# Jacdac_3D_Magnetometer.net
KiCad netlist of a schematic drawn in EAGLE
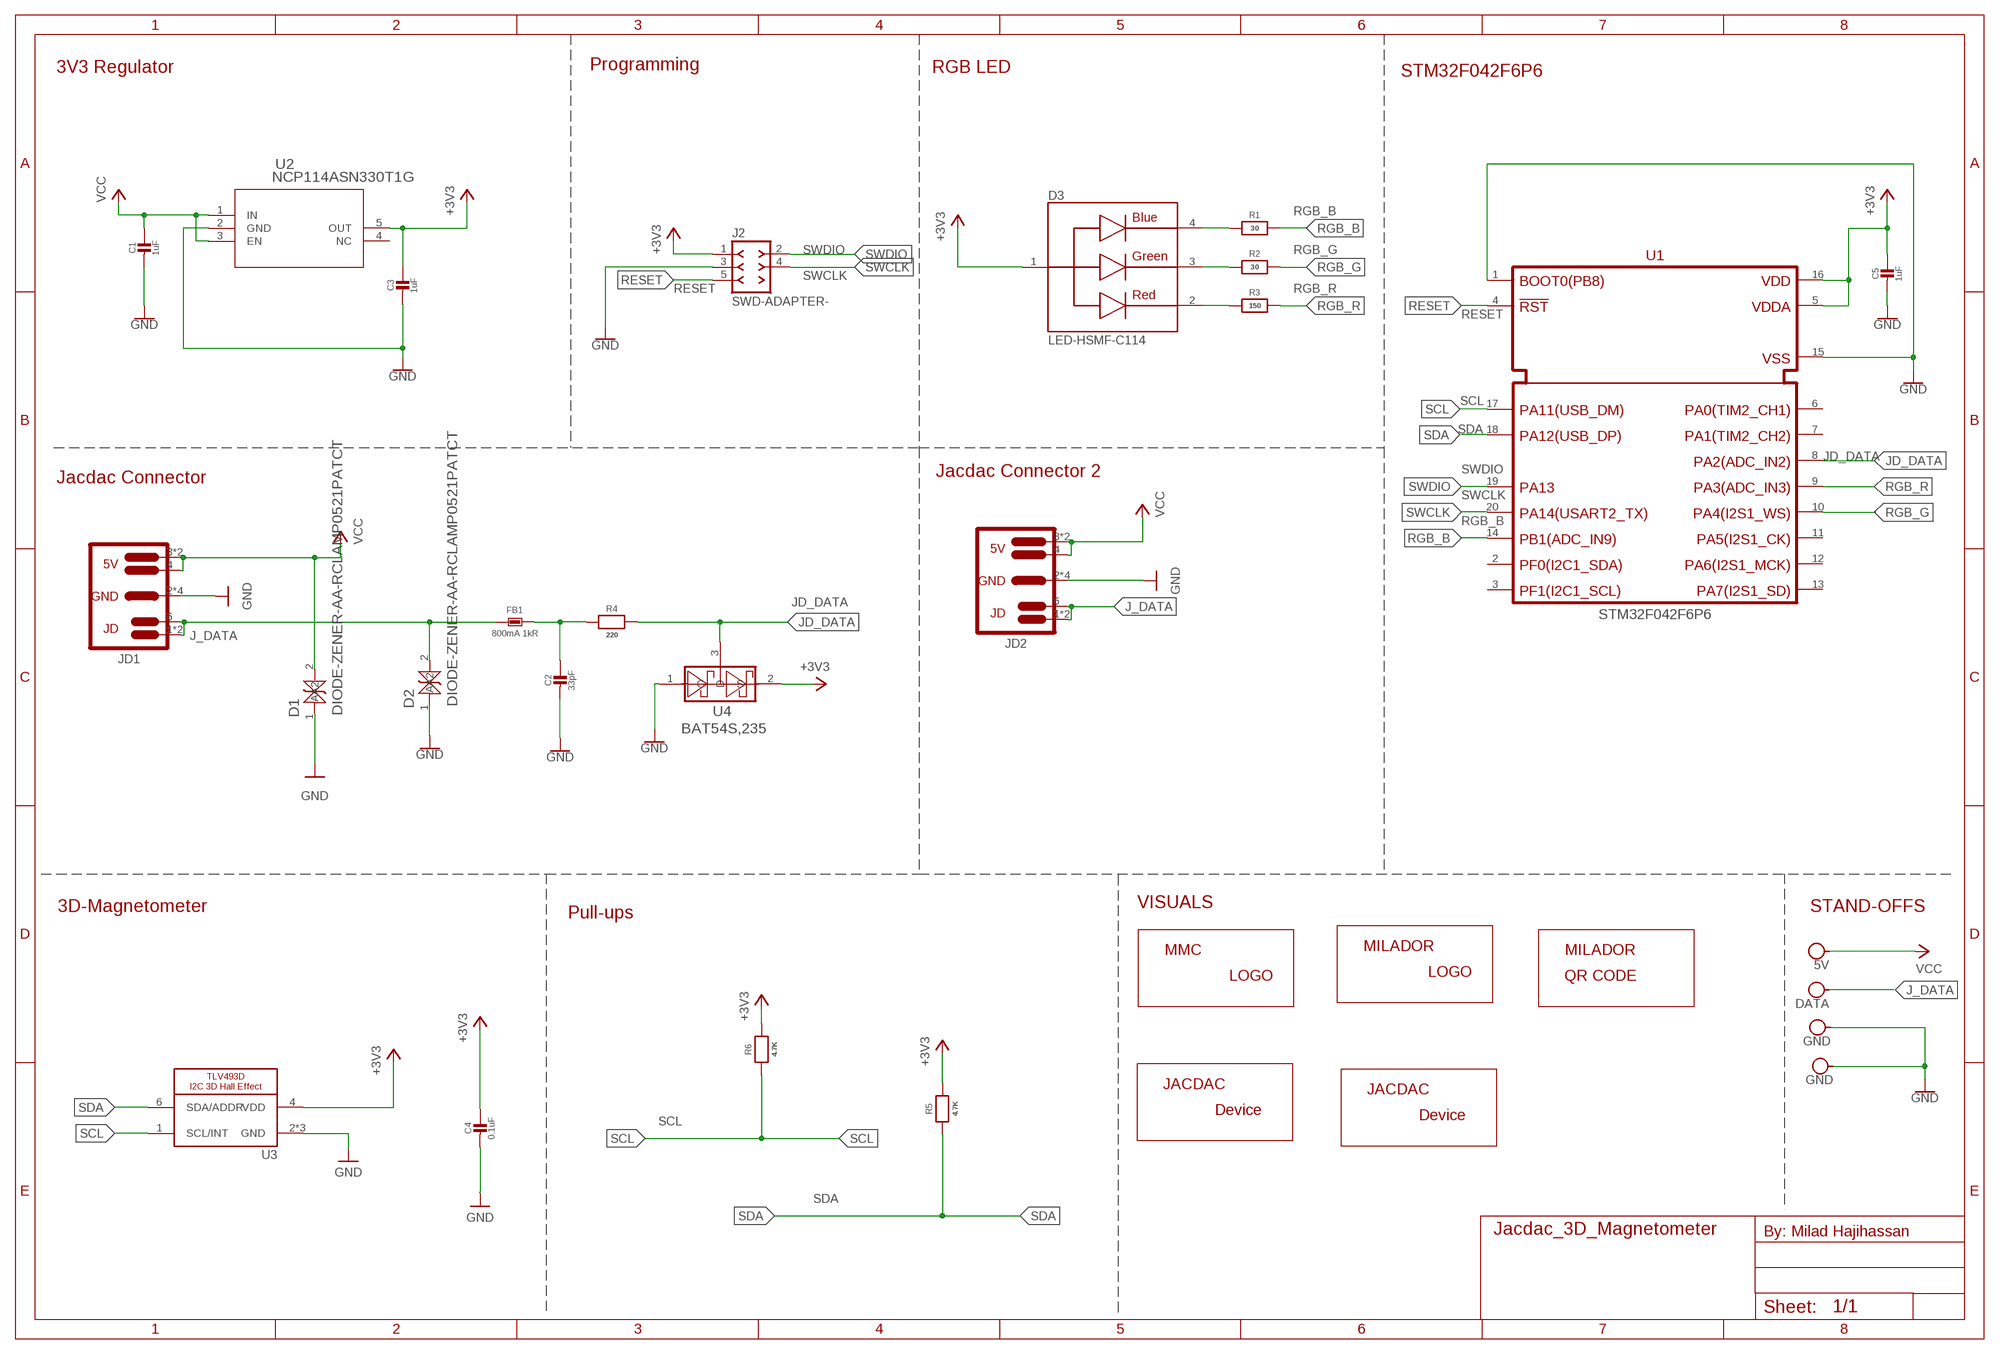
[diagram p0: schematic, sheet 1]

(export (version "E")
  (design (tool "Eeschema 10.0.6"))
  (components
    (comp (ref "C1")
      (value "1uF")
      (footprint "eagle-import:0603-NO")
      (libsource (lib "eagle-import") (part "CAP_CERAMIC-0603-NO"))
    )
    (comp (ref "C2")
      (value "33pF")
      (footprint "eagle-import:0603")
      (libsource (lib "eagle-import") (part "CAP_CERAMIC-0603"))
    )
    (comp (ref "C3")
      (value "1uF")
      (footprint "eagle-import:0603-NO")
      (libsource (lib "eagle-import") (part "CAP_CERAMIC-0603-NO"))
    )
    (comp (ref "C4")
      (value "0.1uF")
      (footprint "eagle-import:0603-NO")
      (libsource (lib "eagle-import") (part "CAP_CERAMIC-0603-NO"))
    )
    (comp (ref "C5")
      (value "1uF")
      (footprint "eagle-import:0603")
      (libsource (lib "eagle-import") (part "CAP_CERAMIC-0603"))
    )
    (comp (ref "D1")
      (value "DIODE-ZENER-AA-RCLAMP0521PATCT")
      (footprint "eagle-import:DIODE-ZENER-0402")
      (fields
        (field (name "MANUFACTURER_PART_NUMBER") "RCLAMP0521PATCT")
        (field (name "COPYRIGHT") "Copyright (C) 2021 Ultra Librarian. All rights reserved.")
      )
      (libsource (lib "eagle-import") (part "DIODE-ZENER-AA-RCLAMP0521PATCT"))
    )
    (comp (ref "D2")
      (value "DIODE-ZENER-AA-RCLAMP0521PATCT")
      (footprint "eagle-import:DIODE-ZENER-0402")
      (fields
        (field (name "MANUFACTURER_PART_NUMBER") "RCLAMP0521PATCT")
        (field (name "COPYRIGHT") "Copyright (C) 2021 Ultra Librarian. All rights reserved.")
      )
      (libsource (lib "eagle-import") (part "DIODE-ZENER-AA-RCLAMP0521PATCT"))
    )
    (comp (ref "D3")
      (value "LED-HSMF-C114")
      (footprint "eagle-import:DIOSC160X150X35-4N")
      (fields (field (name "MF") "Broadcom Limited") (field (name "MP") "HSMF-C114"))
      (libsource (lib "eagle-import") (part "LED-HSMF-C114"))
    )
    (comp (ref "FB1")
      (value "800mA 1kR")
      (footprint "eagle-import:0603-NO")
      (libsource (lib "eagle-import") (part "FERRITE-BEAD-0603-NO"))
    )
    (comp (ref "J2")
      (value "SWD-ADAPTER-")
      (footprint "eagle-import:SWD-ADAPTER")
      (libsource (lib "eagle-import") (part "SWD-ADAPTER-"))
    )
    (comp (ref "J3")
      (value "5V")
      (footprint "eagle-import:M3-HOLE-PWR-OUTL")
      (libsource (lib "eagle-import") (part "JACDAC-M3-PWR-OUTL"))
    )
    (comp (ref "J4")
      (value "DATA")
      (footprint "eagle-import:M3-HOLE-DATA-NOTCH")
      (libsource (lib "eagle-import") (part "JACDAC-M3-DATA-NOTCH"))
    )
    (comp (ref "J5")
      (value "GND")
      (footprint "eagle-import:M3-HOLE-GND")
      (libsource (lib "eagle-import") (part "JACDAC-M3-GND"))
    )
    (comp (ref "J6")
      (value "GND")
      (footprint "eagle-import:M3-HOLE-GND")
      (libsource (lib "eagle-import") (part "JACDAC-M3-GND"))
    )
    (comp (ref "JD1")
      (value "JACDAC-EDGE-OUTIE")
      (footprint "eagle-import:JD-EDGE-OUTIE")
      (libsource (lib "eagle-import") (part "JACDAC-EDGE-OUTIE"))
    )
    (comp (ref "JD2")
      (value "JACDAC-EDGE-OUTIE")
      (footprint "eagle-import:JD-EDGE-OUTIE")
      (libsource (lib "eagle-import") (part "JACDAC-EDGE-OUTIE"))
    )
    (comp (ref "LABEL_JACDAC_PS")
      (value "MILADOR-JACDAC-DEVICE-MAGNETOMETER")
      (footprint "eagle-import:JACDAC-3D-MAGNETOMETER")
      (libsource (lib "eagle-import") (part "MILADOR-JACDAC-DEVICE-MAGNETOMETER"))
    )
    (comp (ref "LABEL_MILADOR")
      (value "MILADOR-LOGO-")
      (footprint "eagle-import:MILADOR_LOGO1")
      (libsource (lib "eagle-import") (part "MILADOR-LOGO-"))
    )
    (comp (ref "LABEL_QR_CODE")
      (value "MILADOR-QR-CODE-JACDAC-MAGNETOMETER")
      (footprint "eagle-import:MILADOR_QR_JACDAC_MAGNETOMETER")
      (libsource (lib "eagle-import") (part "MILADOR-QR-CODE-JACDAC-MAGNETOMETER"))
    )
    (comp (ref "LABEL_TLV493D")
      (value "MILADOR-JACDAC-DEVICE-TLV493D")
      (footprint "eagle-import:JACDAC-TLV493D")
      (libsource (lib "eagle-import") (part "MILADOR-JACDAC-DEVICE-TLV493D"))
    )
    (comp (ref "MMC_LOGO")
      (value "MMC_LOGO-XSM")
      (footprint "eagle-import:MMC_X-SMALL_LOGO")
      (libsource (lib "eagle-import") (part "MMC_LOGO-XSM"))
    )
    (comp (ref "R1")
      (value "30")
      (footprint "eagle-import:0603")
      (libsource (lib "eagle-import") (part "RESISTOR-0603"))
    )
    (comp (ref "R2")
      (value "30")
      (footprint "eagle-import:0603")
      (libsource (lib "eagle-import") (part "RESISTOR-0603"))
    )
    (comp (ref "R3")
      (value "150")
      (footprint "eagle-import:0603")
      (libsource (lib "eagle-import") (part "RESISTOR-0603"))
    )
    (comp (ref "R4")
      (value "220")
      (footprint "eagle-import:0603")
      (libsource (lib "eagle-import") (part "RESISTOR-0603"))
    )
    (comp (ref "R5")
      (value "4.7K")
      (footprint "eagle-import:0603")
      (libsource (lib "eagle-import") (part "RESISTOR-0603"))
    )
    (comp (ref "R6")
      (value "4.7K")
      (footprint "eagle-import:0603")
      (libsource (lib "eagle-import") (part "RESISTOR-0603"))
    )
    (comp (ref "U1")
      (value "STM32F042F6P6")
      (footprint "eagle-import:TSSOP20")
      (libsource (lib "eagle-import") (part "STM32F042F6P6"))
    )
    (comp (ref "U2")
      (value "NCP114ASN330T1G")
      (footprint "eagle-import:TSOP-5_ONS")
      (fields (field (name "COPYRIGHT") "Copyright (C) 2021 Ultra Librarian. All rights reserved."))
      (libsource (lib "eagle-import") (part "NCP114ASN330T1G"))
    )
    (comp (ref "U3")
      (value "TLV493D")
      (footprint "eagle-import:SOT23-6")
      (libsource (lib "eagle-import") (part "TLV493D"))
    )
    (comp (ref "U4")
      (value "BAT54S,235")
      (footprint "eagle-import:SOT23-3")
      (fields (field (name "MF") "Diodes") (field (name "MP") "BSS138-7-F"))
      (libsource (lib "eagle-import") (part "BAT54S,235"))
    )
  )
  (nets
    (net (code "1") (name "+3V3") (class "Default")
      (node (ref "C3") (pin "1") (pinfunction "1_1") (pintype "passive"))
      (node (ref "C4") (pin "1") (pinfunction "1_1") (pintype "passive"))
      (node (ref "C5") (pin "1") (pinfunction "1_1") (pintype "passive"))
      (node (ref "D3") (pin "1") (pinfunction "1_1") (pintype "passive"))
      (node (ref "J2") (pin "1") (pinfunction "VCC_1_1") (pintype "passive"))
      (node (ref "R5") (pin "2") (pinfunction "2_2") (pintype "passive"))
      (node (ref "R6") (pin "2") (pinfunction "2_2") (pintype "passive"))
      (node (ref "U1") (pin "16") (pinfunction "VDD_16") (pintype "input"))
      (node (ref "U1") (pin "5") (pinfunction "VDDA_5") (pintype "input"))
      (node (ref "U2") (pin "5") (pinfunction "OUT_5") (pintype "power_in"))
      (node (ref "U3") (pin "4") (pinfunction "VDD_4") (pintype "power_in"))
      (node (ref "U4") (pin "2") (pinfunction "S_2") (pintype "passive"))
    )
    (net (code "2") (name "GND") (class "Default")
      (node (ref "C1") (pin "2") (pinfunction "2_2") (pintype "passive"))
      (node (ref "C2") (pin "2") (pinfunction "2_2") (pintype "passive"))
      (node (ref "C3") (pin "2") (pinfunction "2_2") (pintype "passive"))
      (node (ref "C4") (pin "2") (pinfunction "2_2") (pintype "passive"))
      (node (ref "C5") (pin "2") (pinfunction "2_2") (pintype "passive"))
      (node (ref "D1") (pin "1") (pinfunction "A_1") (pintype "passive"))
      (node (ref "D2") (pin "1") (pinfunction "A_1") (pintype "passive"))
      (node (ref "J2") (pin "3") (pinfunction "GND_3_3") (pintype "passive"))
      (node (ref "J5") (pin "H") (pinfunction "P$1_H") (pintype "bidirectional"))
      (node (ref "J6") (pin "H") (pinfunction "P$1_H") (pintype "bidirectional"))
      (node (ref "JD1") (pin "2") (pinfunction "1_2") (pintype "power_in"))
      (node (ref "JD1") (pin "5") (pinfunction "1_5") (pintype "power_in"))
      (node (ref "JD1") (pin "P$2") (pinfunction "1_P$2") (pintype "power_in"))
      (node (ref "JD1") (pin "P$4") (pinfunction "1_P$4") (pintype "power_in"))
      (node (ref "JD2") (pin "2") (pinfunction "1_2") (pintype "power_in"))
      (node (ref "JD2") (pin "5") (pinfunction "1_5") (pintype "power_in"))
      (node (ref "JD2") (pin "P$2") (pinfunction "1_P$2") (pintype "power_in"))
      (node (ref "JD2") (pin "P$4") (pinfunction "1_P$4") (pintype "power_in"))
      (node (ref "U1") (pin "1") (pinfunction "BOOT0_1") (pintype "input"))
      (node (ref "U1") (pin "15") (pinfunction "VSS_15") (pintype "input"))
      (node (ref "U2") (pin "2") (pinfunction "GND_2") (pintype "passive"))
      (node (ref "U3") (pin "2") (pinfunction "GND_2") (pintype "power_in"))
      (node (ref "U3") (pin "3") (pinfunction "GND_3") (pintype "power_in"))
      (node (ref "U3") (pin "5") (pinfunction "GND_5") (pintype "power_in"))
      (node (ref "U4") (pin "1") (pinfunction "G_1") (pintype "passive"))
    )
    (net (code "3") (name "JD_DATA") (class "Default")
      (node (ref "R4") (pin "2") (pinfunction "2_2") (pintype "passive"))
      (node (ref "U1") (pin "8") (pinfunction "PA2_8") (pintype "bidirectional"))
      (node (ref "U4") (pin "3") (pinfunction "D_3") (pintype "passive"))
    )
    (net (code "4") (name "J_DATA") (class "Default")
      (node (ref "D2") (pin "2") (pinfunction "A2_2") (pintype "passive"))
      (node (ref "FB1") (pin "2") (pinfunction "2_2") (pintype "passive"))
      (node (ref "J4") (pin "H") (pinfunction "P$1_H") (pintype "bidirectional"))
      (node (ref "JD1") (pin "1") (pinfunction "2_1") (pintype "bidirectional"))
      (node (ref "JD1") (pin "6") (pinfunction "6_6") (pintype "bidirectional"))
      (node (ref "JD1") (pin "P$3") (pinfunction "2_P$3") (pintype "bidirectional"))
      (node (ref "JD2") (pin "1") (pinfunction "2_1") (pintype "bidirectional"))
      (node (ref "JD2") (pin "6") (pinfunction "6_6") (pintype "bidirectional"))
      (node (ref "JD2") (pin "P$3") (pinfunction "2_P$3") (pintype "bidirectional"))
    )
    (net (code "5") (name "Net-(C2-Pad1)") (class "Default")
      (node (ref "C2") (pin "1") (pinfunction "1_1") (pintype "passive"))
      (node (ref "FB1") (pin "1") (pinfunction "1_1") (pintype "passive"))
      (node (ref "R4") (pin "1") (pinfunction "1_1") (pintype "passive"))
    )
    (net (code "6") (name "Net-(D3-Pad2)") (class "Default")
      (node (ref "D3") (pin "2") (pinfunction "2_2") (pintype "passive"))
      (node (ref "R3") (pin "1") (pinfunction "1_1") (pintype "passive"))
    )
    (net (code "7") (name "Net-(D3-Pad3)") (class "Default")
      (node (ref "D3") (pin "3") (pinfunction "3_3") (pintype "passive"))
      (node (ref "R2") (pin "1") (pinfunction "1_1") (pintype "passive"))
    )
    (net (code "8") (name "Net-(D3-Pad4)") (class "Default")
      (node (ref "D3") (pin "4") (pinfunction "4_4") (pintype "passive"))
      (node (ref "R1") (pin "1") (pinfunction "1_1") (pintype "passive"))
    )
    (net (code "9") (name "RESET") (class "Default")
      (node (ref "J2") (pin "5") (pinfunction "RESET_5_5") (pintype "passive"))
      (node (ref "U1") (pin "4") (pinfunction "~{RST}_4") (pintype "input"))
    )
    (net (code "10") (name "RGB_B") (class "Default")
      (node (ref "R1") (pin "2") (pinfunction "2_2") (pintype "passive"))
      (node (ref "U1") (pin "14") (pinfunction "PB1_14") (pintype "bidirectional"))
    )
    (net (code "11") (name "RGB_G") (class "Default")
      (node (ref "R2") (pin "2") (pinfunction "2_2") (pintype "passive"))
      (node (ref "U1") (pin "10") (pinfunction "PA4_10") (pintype "bidirectional"))
    )
    (net (code "12") (name "RGB_R") (class "Default")
      (node (ref "R3") (pin "2") (pinfunction "2_2") (pintype "passive"))
      (node (ref "U1") (pin "9") (pinfunction "PA3_9") (pintype "bidirectional"))
    )
    (net (code "13") (name "SCL") (class "Default")
      (node (ref "R6") (pin "1") (pinfunction "1_1") (pintype "passive"))
      (node (ref "U1") (pin "17") (pinfunction "PA11_17") (pintype "bidirectional"))
      (node (ref "U3") (pin "1") (pinfunction "SCL/INT_1") (pintype "bidirectional"))
    )
    (net (code "14") (name "SDA") (class "Default")
      (node (ref "R5") (pin "1") (pinfunction "1_1") (pintype "passive"))
      (node (ref "U1") (pin "18") (pinfunction "PA12_18") (pintype "bidirectional"))
      (node (ref "U3") (pin "6") (pinfunction "SDA/ADDR_6") (pintype "bidirectional"))
    )
    (net (code "15") (name "SWCLK") (class "Default")
      (node (ref "J2") (pin "4") (pinfunction "SWCLK_4_4") (pintype "passive"))
      (node (ref "U1") (pin "20") (pinfunction "PA14_20") (pintype "bidirectional"))
    )
    (net (code "16") (name "SWDIO") (class "Default")
      (node (ref "J2") (pin "2") (pinfunction "SWDIO_2_2") (pintype "passive"))
      (node (ref "U1") (pin "19") (pinfunction "PA13_19") (pintype "bidirectional"))
    )
    (net (code "17") (name "VCC") (class "Default")
      (node (ref "C1") (pin "1") (pinfunction "1_1") (pintype "passive"))
      (node (ref "D1") (pin "2") (pinfunction "A2_2") (pintype "passive"))
      (node (ref "J3") (pin "H") (pinfunction "P$1_H") (pintype "bidirectional"))
      (node (ref "JD1") (pin "3") (pinfunction "3_3") (pintype "power_in"))
      (node (ref "JD1") (pin "4") (pinfunction "4_4") (pintype "power_in"))
      (node (ref "JD1") (pin "P$1") (pinfunction "3_P$1") (pintype "power_in"))
      (node (ref "JD2") (pin "3") (pinfunction "3_3") (pintype "power_in"))
      (node (ref "JD2") (pin "4") (pinfunction "4_4") (pintype "power_in"))
      (node (ref "JD2") (pin "P$1") (pinfunction "3_P$1") (pintype "power_in"))
      (node (ref "U2") (pin "1") (pinfunction "IN_1") (pintype "input"))
      (node (ref "U2") (pin "3") (pinfunction "EN_3") (pintype "passive"))
    )
    (net (code "18") (name "unconnected-(U1-PA0-Pad6)") (class "Default")
      (node (ref "U1") (pin "6") (pinfunction "PA0_6") (pintype "bidirectional"))
    )
    (net (code "19") (name "unconnected-(U1-PA1-Pad7)") (class "Default")
      (node (ref "U1") (pin "7") (pinfunction "PA1_7") (pintype "bidirectional"))
    )
    (net (code "20") (name "unconnected-(U1-PA5-Pad11)") (class "Default")
      (node (ref "U1") (pin "11") (pinfunction "PA5_11") (pintype "bidirectional"))
    )
    (net (code "21") (name "unconnected-(U1-PA6-Pad12)") (class "Default")
      (node (ref "U1") (pin "12") (pinfunction "PA6_12") (pintype "bidirectional"))
    )
    (net (code "22") (name "unconnected-(U1-PA7-Pad13)") (class "Default")
      (node (ref "U1") (pin "13") (pinfunction "PA7_13") (pintype "bidirectional"))
    )
    (net (code "23") (name "unconnected-(U1-PF0-Pad2)") (class "Default")
      (node (ref "U1") (pin "2") (pinfunction "PF0_2") (pintype "bidirectional"))
    )
    (net (code "24") (name "unconnected-(U1-PF1-Pad3)") (class "Default")
      (node (ref "U1") (pin "3") (pinfunction "PF1_3") (pintype "bidirectional"))
    )
    (net (code "25") (name "unconnected-(U2-NC-Pad4)") (class "Default")
      (node (ref "U2") (pin "4") (pinfunction "NC_4") (pintype "no_connect"))
    )
  )
)
